# LIS3MDL.net
KiCad netlist of a schematic drawn in Altium Designer
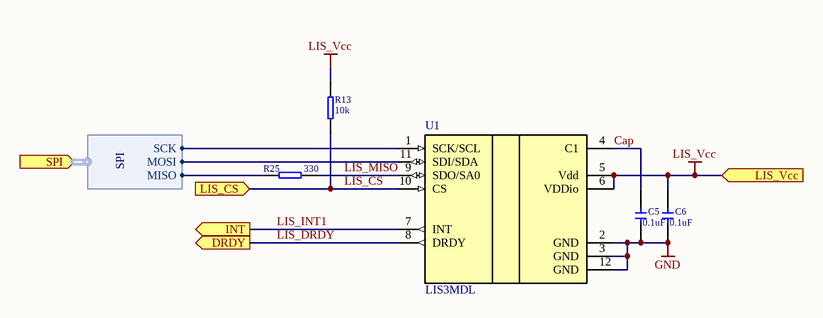
[diagram p0: LIS3MDL.SchDoc]

(export (version "E")
  (design (tool "Eeschema 10.0.6"))
  (components
    (comp (ref "C5")
      (value "0.1uF")
      (footprint "CERCAP 0603")
      (description "Capacitor")
      (fields (field (name "Comment") "CERCAP 0603 0.1uF * X7R"))
      (libsource (lib "!main") (part "!Capacitor"))
    )
    (comp (ref "C6")
      (value "0.1uF")
      (footprint "CERCAP 0603")
      (description "Capacitor")
      (fields (field (name "Comment") "CERCAP 0603 0.1uF * X7R"))
      (libsource (lib "!main") (part "!Capacitor"))
    )
    (comp (ref "R13")
      (value "10k")
      (footprint "RES 0603")
      (description "Resistor")
      (fields (field (name "Comment") "RES 0603 10k"))
      (libsource (lib "!main") (part "!Resistor"))
    )
    (comp (ref "R25")
      (value "330")
      (footprint "RES 0603")
      (description "Resistor")
      (fields (field (name "Comment") "RES 0603 330"))
      (libsource (lib "!main") (part "!Resistor"))
    )
    (comp (ref "U1")
      (value "LIS3MDL")
      (footprint "LGA12_LIS3MDL")
      (description "Mag")
      (libsource (lib "sensors") (part "LIS3MDL"))
    )
  )
  (nets
    (net (code "2") (name "/Cap") (class "Default")
      (node (ref "C5") (pin "2") (pintype "passive"))
      (node (ref "U1") (pin "4") (pinfunction "C1_4") (pintype "power_in"))
    )
    (net (code "3") (name "/LIS_CS") (class "Default")
      (node (ref "R13") (pin "1") (pinfunction "11_1") (pintype "passive"))
      (node (ref "U1") (pin "10") (pinfunction "CS_10") (pintype "input"))
    )
    (net (code "4") (name "/LIS_DRDY") (class "Default")
      (node (ref "U1") (pin "8") (pinfunction "DRDY_8") (pintype "output"))
    )
    (net (code "5") (name "/LIS_INT1") (class "Default")
      (node (ref "U1") (pin "7") (pinfunction "INT_7") (pintype "output"))
    )
    (net (code "6") (name "/LIS_MISO") (class "Default")
      (node (ref "R25") (pin "1") (pinfunction "11_1") (pintype "passive"))
      (node (ref "U1") (pin "9") (pinfunction "SDO/SA0_9") (pintype "bidirectional"))
    )
    (net (code "7") (name "/MISO") (class "Default")
      (node (ref "R25") (pin "2") (pinfunction "12_2") (pintype "passive"))
    )
    (net (code "8") (name "/MOSI") (class "Default")
      (node (ref "U1") (pin "11") (pinfunction "SDI/SDA_11") (pintype "bidirectional"))
    )
    (net (code "9") (name "/SCK") (class "Default")
      (node (ref "U1") (pin "1") (pinfunction "SCK/SCL_1") (pintype "input"))
    )
    (net (code "11") (name "GND") (class "Default")
      (node (ref "C5") (pin "1") (pintype "passive"))
      (node (ref "C6") (pin "1") (pintype "passive"))
      (node (ref "U1") (pin "12") (pinfunction "GND_12") (pintype "power_in"))
      (node (ref "U1") (pin "2") (pinfunction "GND_2") (pintype "power_in"))
      (node (ref "U1") (pin "3") (pinfunction "GND_3") (pintype "power_in"))
    )
    (net (code "12") (name "LIS_Vcc") (class "Default")
      (node (ref "C6") (pin "2") (pintype "passive"))
      (node (ref "R13") (pin "2") (pinfunction "12_2") (pintype "passive"))
      (node (ref "U1") (pin "5") (pinfunction "Vdd_5") (pintype "power_in"))
      (node (ref "U1") (pin "6") (pinfunction "VDDio_6") (pintype "power_in"))
    )
  )
)
